# 4_bat_input_power_monitor.net
KiCad netlist of a schematic drawn in Altium Designer
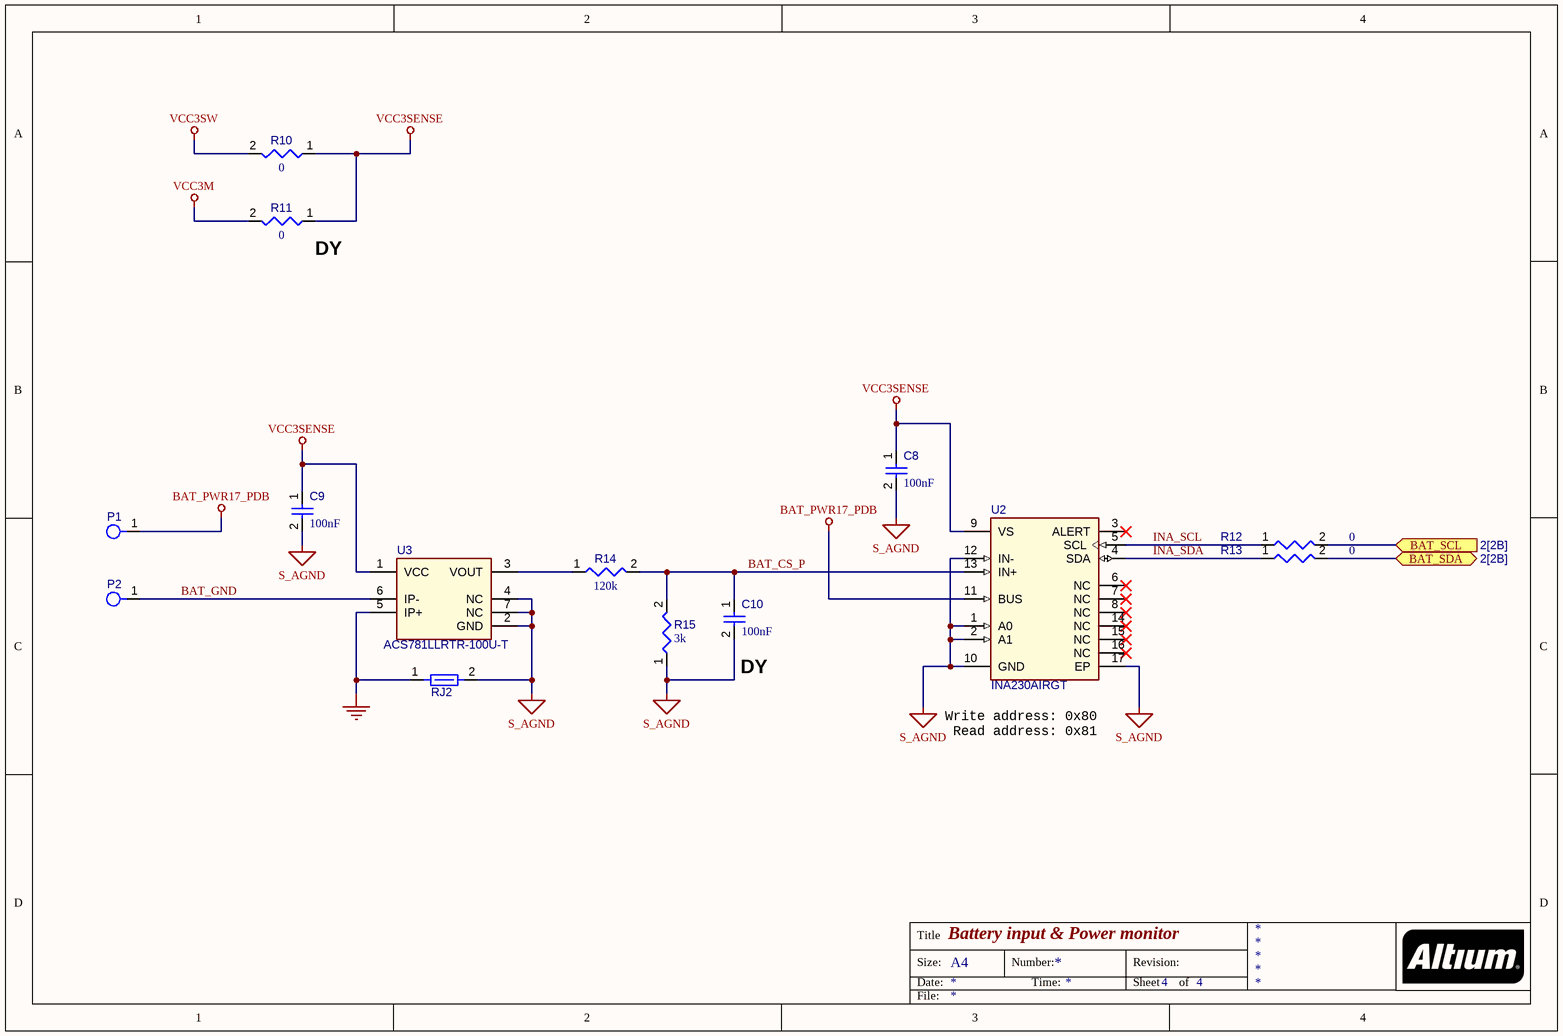
[diagram p0: 4_bat_input&power_monitor.SchDoc]

(export (version "E")
  (design (tool "Eeschema 10.0.6"))
  (components
    (comp (ref "C8")
      (value "100nF")
      (footprint "CAPC0402(1005)60_L")
      (description "Chip Capacitor, 100nF +/-20%, 50V, 0402, Thickness 0.6 mm")
      (fields (field (name "TOLERANCE") "10%") (field (name "Comment") "Capacitor 100nF +/-20% 50V 0402"))
      (libsource (lib "<Company> Server") (part "CAP-NP-2"))
    )
    (comp (ref "C9")
      (value "100nF")
      (footprint "CAPC0402(1005)60_L")
      (description "Chip Capacitor, 100nF +/-20%, 50V, 0402, Thickness 0.6 mm")
      (fields (field (name "TOLERANCE") "10%") (field (name "Comment") "Capacitor 100nF +/-20% 50V 0402"))
      (libsource (lib "<Company> Server") (part "CAP-NP-2"))
    )
    (comp (ref "C10")
      (value "100nF")
      (footprint "CAPC0402(1005)60_L")
      (description "Chip Capacitor, 100nF +/-20%, 50V, 0402, Thickness 0.6 mm")
      (fields (field (name "TOLERANCE") "10%") (field (name "Comment") "Capacitor 100nF +/-20% 50V 0402"))
      (libsource (lib "<Company> Server") (part "CAP-NP-2"))
    )
    (comp (ref "P1")
      (value "WIRE_PAD_7x4")
      (footprint "WIRE_PAD_7x4-Footprint-1")
      (description "SMD WIRE PAD 7 x 4 mm")
      (libsource (lib "<Company> Server") (part "CMP-001-0023-7"))
    )
    (comp (ref "P2")
      (value "WIRE_PAD_7x4")
      (footprint "WIRE_PAD_7x4-Footprint-1")
      (description "SMD WIRE PAD 7 x 4 mm")
      (libsource (lib "<Company> Server") (part "CMP-001-0023-7"))
    )
    (comp (ref "R10")
      (value "0")
      (footprint "RESC0402(1005)_L")
      (description "Jumper 0402")
      (libsource (lib "<Company> Server") (part "RES-2"))
    )
    (comp (ref "R11")
      (value "0")
      (footprint "RESC0402(1005)_L")
      (description "Jumper 0402")
      (libsource (lib "<Company> Server") (part "RES-2"))
    )
    (comp (ref "R12")
      (value "0")
      (footprint "RESC0402(1005)_L")
      (description "Jumper 0402")
      (libsource (lib "<Company> Server") (part "RES-2"))
    )
    (comp (ref "R13")
      (value "0")
      (footprint "RESC0402(1005)_L")
      (description "Jumper 0402")
      (libsource (lib "<Company> Server") (part "RES-2"))
    )
    (comp (ref "R14")
      (value "120k")
      (footprint "RESC0402(1005)_L")
      (description "Chip Resistor, 120 kOhms, +/-1 %, 63 mW, -55 to 155 degC, 0402")
      (fields (field (name "TOLERANCE") "1%") (field (name "POWER") "63mW"))
      (libsource (lib "<Company> Server") (part "RES-2"))
    )
    (comp (ref "R15")
      (value "3k")
      (footprint "RESC0402(1005)_L")
      (description "Chip Resistor, 3 kOhms, +/-1 %, 63 mW, -55 to 155 degC, 0402")
      (fields (field (name "POWER") "63mW") (field (name "TOLERANCE") "1%"))
      (libsource (lib "<Company> Server") (part "RES-2"))
    )
    (comp (ref "RJ2")
      (value "Net Tie 10x8mil")
      (footprint "New footprint 1")
      (libsource (lib "<Company> Server") (part "CMP-00022-00002-2"))
    )
    (comp (ref "U2")
      (value "INA230AIRGT")
      (footprint "RGT0016C_V")
      (description "High or Low Side Measurement, 2.7 to 5.5 V, -40 to 125 degC, 16-Pin QFN, RoHS, Tape and Reel")
      (libsource (lib "<Company> Server") (part "CMP-02186-6"))
    )
    (comp (ref "U3")
      (value "ACS781LLRTR-100U-T")
      (footprint "ALEG-PSOF-7_V")
      (libsource (lib "<Company> Server") (part "CMP-02178-6"))
    )
  )
  (nets
    (net (code "1") (name "/BAT_CS_P") (class "Default")
      (node (ref "C10") (pin "1") (pinfunction "1_1") (pintype "passive"))
      (node (ref "R14") (pin "2") (pinfunction "2_2") (pintype "passive"))
      (node (ref "R15") (pin "2") (pinfunction "2_2") (pintype "passive"))
      (node (ref "U2") (pin "13") (pinfunction "IN+_13") (pintype "input"))
    )
    (net (code "2") (name "/BAT_GND") (class "Default")
      (node (ref "P2") (pin "1") (pinfunction "H1_1") (pintype "passive"))
      (node (ref "U3") (pin "6") (pinfunction "IP-_6") (pintype "passive"))
    )
    (net (code "3") (name "/BAT_SCL") (class "Default")
      (node (ref "R12") (pin "2") (pinfunction "2_2") (pintype "passive"))
    )
    (net (code "4") (name "/BAT_SDA") (class "Default")
      (node (ref "R13") (pin "2") (pinfunction "2_2") (pintype "passive"))
    )
    (net (code "5") (name "/INA_SCL") (class "Default")
      (node (ref "R12") (pin "1") (pinfunction "1_1") (pintype "passive"))
      (node (ref "U2") (pin "5") (pinfunction "SCL_5") (pintype "input"))
    )
    (net (code "6") (name "/INA_SDA") (class "Default")
      (node (ref "R13") (pin "1") (pinfunction "1_1") (pintype "passive"))
      (node (ref "U2") (pin "4") (pinfunction "SDA_4") (pintype "bidirectional"))
    )
    (net (code "7") (name "BAT_PWR17_PDB") (class "Default")
      (node (ref "P1") (pin "1") (pinfunction "H1_1") (pintype "passive"))
      (node (ref "U2") (pin "11") (pinfunction "BUS_11") (pintype "input"))
    )
    (net (code "8") (name "GND") (class "Default")
      (node (ref "RJ2") (pin "1") (pinfunction "1_1") (pintype "passive"))
      (node (ref "U3") (pin "5") (pinfunction "IP+_5") (pintype "passive"))
    )
    (net (code "9") (name "Net-(U3-VOUT)") (class "Default")
      (node (ref "R14") (pin "1") (pinfunction "1_1") (pintype "passive"))
      (node (ref "U3") (pin "3") (pinfunction "VOUT_3") (pintype "power_in"))
    )
    (net (code "10") (name "S_AGND") (class "Default")
      (node (ref "C10") (pin "2") (pinfunction "2_2") (pintype "passive"))
      (node (ref "C8") (pin "2") (pinfunction "2_2") (pintype "passive"))
      (node (ref "C9") (pin "2") (pinfunction "2_2") (pintype "passive"))
      (node (ref "R15") (pin "1") (pinfunction "1_1") (pintype "passive"))
      (node (ref "RJ2") (pin "2") (pinfunction "2_2") (pintype "passive"))
      (node (ref "U2") (pin "1") (pinfunction "A0_1") (pintype "input"))
      (node (ref "U2") (pin "10") (pinfunction "GND_10") (pintype "power_in"))
      (node (ref "U2") (pin "12") (pinfunction "IN-_12") (pintype "input"))
      (node (ref "U2") (pin "17") (pinfunction "EP_17") (pintype "power_in"))
      (node (ref "U2") (pin "2") (pinfunction "A1_2") (pintype "input"))
      (node (ref "U3") (pin "2") (pinfunction "GND_2") (pintype "power_in"))
      (node (ref "U3") (pin "4") (pinfunction "NC_4") (pintype "passive"))
      (node (ref "U3") (pin "7") (pinfunction "NC_7") (pintype "passive"))
    )
    (net (code "11") (name "VCC3M") (class "Default")
      (node (ref "R11") (pin "2") (pinfunction "2_2") (pintype "passive"))
    )
    (net (code "12") (name "VCC3SENSE") (class "Default")
      (node (ref "C8") (pin "1") (pinfunction "1_1") (pintype "passive"))
      (node (ref "C9") (pin "1") (pinfunction "1_1") (pintype "passive"))
      (node (ref "R10") (pin "1") (pinfunction "1_1") (pintype "passive"))
      (node (ref "R11") (pin "1") (pinfunction "1_1") (pintype "passive"))
      (node (ref "U2") (pin "9") (pinfunction "VS_9") (pintype "power_in"))
      (node (ref "U3") (pin "1") (pinfunction "VCC_1") (pintype "power_in"))
    )
    (net (code "13") (name "VCC3SW") (class "Default")
      (node (ref "R10") (pin "2") (pinfunction "2_2") (pintype "passive"))
    )
    (net (code "14") (name "unconnected-(U2-ALERT-Pad3)") (class "Default")
      (node (ref "U2") (pin "3") (pinfunction "ALERT_3") (pintype "open_collector+no_connect"))
    )
    (net (code "15") (name "unconnected-(U2-NC-Pad6)") (class "Default")
      (node (ref "U2") (pin "6") (pinfunction "NC_6") (pintype "passive+no_connect"))
    )
    (net (code "16") (name "unconnected-(U2-NC-Pad7)") (class "Default")
      (node (ref "U2") (pin "7") (pinfunction "NC_7") (pintype "passive+no_connect"))
    )
    (net (code "17") (name "unconnected-(U2-NC-Pad8)") (class "Default")
      (node (ref "U2") (pin "8") (pinfunction "NC_8") (pintype "passive+no_connect"))
    )
    (net (code "18") (name "unconnected-(U2-NC-Pad14)") (class "Default")
      (node (ref "U2") (pin "14") (pinfunction "NC_14") (pintype "passive+no_connect"))
    )
    (net (code "19") (name "unconnected-(U2-NC-Pad15)") (class "Default")
      (node (ref "U2") (pin "15") (pinfunction "NC_15") (pintype "passive+no_connect"))
    )
    (net (code "20") (name "unconnected-(U2-NC-Pad16)") (class "Default")
      (node (ref "U2") (pin "16") (pinfunction "NC_16") (pintype "passive+no_connect"))
    )
  )
)
